# RA8D2_MCU_-_Ports.net
KiCad netlist of a schematic drawn in Altium Designer
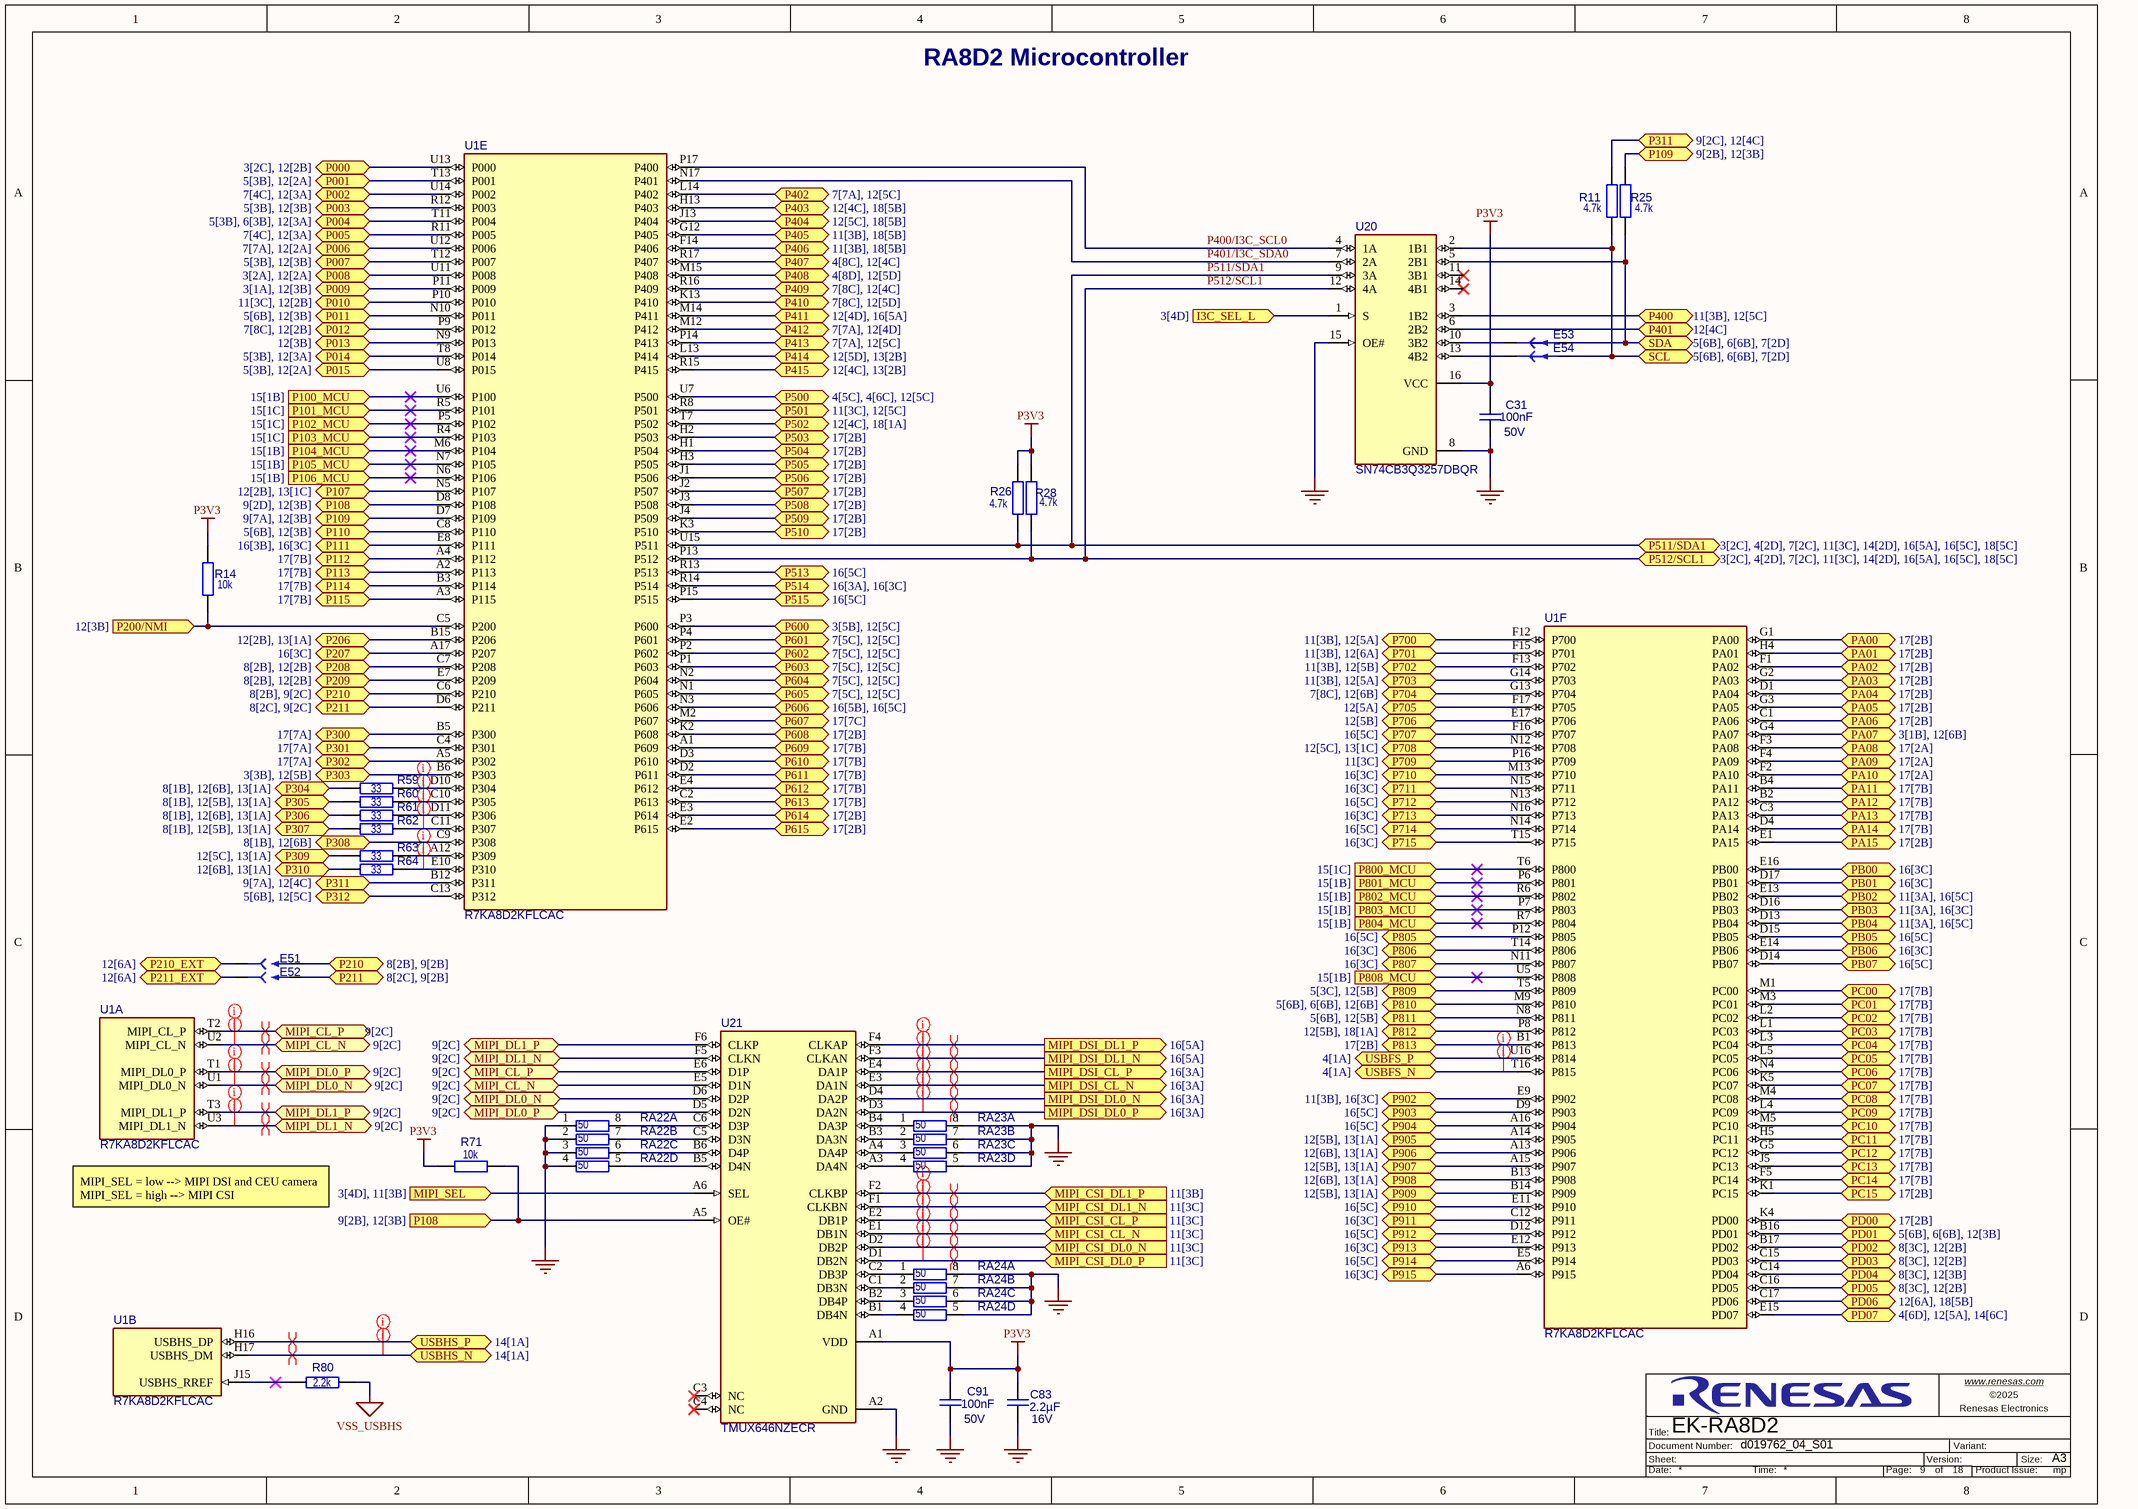
[diagram p0: RA8D2 MCU - Ports.SchDoc]

(export (version "E")
  (design (tool "Eeschema 10.0.6"))
  (components
    (comp (ref "C31")
      (value "100nF")
      (footprint "C_EIA0402_0p55")
      (description "Capacitor,EIA0402,100n,50V,X7R")
      (fields
        (field (name "TOLERANCE") "10%")
        (field (name "OPERATING VOLTAGE MAX") "50V")
        (field (name "Comment") "Capacitor")
      )
      (libsource (lib "ek-ra8d2_mp - Customer") (part "Capacitor"))
    )
    (comp (ref "C83")
      (value "2.2µF")
      (footprint "C_EIA0402_0p7")
      (description "Capacitor,EIA0402,2.2u,16V,X6S")
      (fields
        (field (name "TOLERANCE") "10%")
        (field (name "OPERATING VOLTAGE MAX") "16V")
        (field (name "Comment") "Capacitor")
      )
      (libsource (lib "ek-ra8d2_mp - Customer") (part "Capacitor"))
    )
    (comp (ref "C91")
      (value "100nF")
      (footprint "C_EIA0402_0p55")
      (description "Capacitor,EIA0402,100n,50V,X7R")
      (fields
        (field (name "TOLERANCE") "10%")
        (field (name "OPERATING VOLTAGE MAX") "50V")
        (field (name "Comment") "Capacitor")
      )
      (libsource (lib "ek-ra8d2_mp - Customer") (part "Capacitor"))
    )
    (comp (ref "E51")
      (value "SOLDER_BRIDGE_0805")
      (footprint "solder_bridge_0805")
      (description "Solder Bridge, SMD, 0805 size")
      (libsource (lib "ek-ra8d2_mp - Customer") (part "solder_bridge"))
    )
    (comp (ref "E52")
      (value "SOLDER_BRIDGE_0805")
      (footprint "solder_bridge_0805")
      (description "Solder Bridge, SMD, 0805 size")
      (libsource (lib "ek-ra8d2_mp - Customer") (part "solder_bridge"))
    )
    (comp (ref "E53")
      (value "TRACE_CUT_0805")
      (footprint "trace_cut_0805")
      (description "Trace Cut, SMD, 0805 size")
      (libsource (lib "ek-ra8d2_mp - Customer") (part "trace_cut"))
    )
    (comp (ref "E54")
      (value "TRACE_CUT_0805")
      (footprint "trace_cut_0805")
      (description "Trace Cut, SMD, 0805 size")
      (libsource (lib "ek-ra8d2_mp - Customer") (part "trace_cut"))
    )
    (comp (ref "R11")
      (value "4.7k")
      (footprint "R_EIA0402")
      (description "Resistor,EIA0402,4.7k,0.0625W")
      (fields (field (name "POWER") "62.5mW") (field (name "TOLERANCE") "1%"))
      (libsource (lib "") (part "Resistor_2"))
    )
    (comp (ref "R14")
      (value "10k")
      (footprint "R_EIA0402")
      (description "Resistor,EIA0402,10k,0.0625W")
      (fields (field (name "POWER") "62.5mW") (field (name "TOLERANCE") "1%"))
      (libsource (lib "") (part "Resistor_2"))
    )
    (comp (ref "R25")
      (value "4.7k")
      (footprint "R_EIA0402")
      (description "Resistor,EIA0402,4.7k,0.0625W")
      (fields (field (name "POWER") "62.5mW") (field (name "TOLERANCE") "1%"))
      (libsource (lib "") (part "Resistor_2"))
    )
    (comp (ref "R26")
      (value "4.7k")
      (footprint "R_EIA0402")
      (description "Resistor,EIA0402,4.7k,0.0625W")
      (fields (field (name "POWER") "62.5mW") (field (name "TOLERANCE") "1%"))
      (libsource (lib "") (part "Resistor_2"))
    )
    (comp (ref "R28")
      (value "4.7k")
      (footprint "R_EIA0402")
      (description "Resistor,EIA0402,4.7k,0.0625W")
      (fields (field (name "POWER") "62.5mW") (field (name "TOLERANCE") "1%"))
      (libsource (lib "") (part "Resistor_2"))
    )
    (comp (ref "R59")
      (value "33")
      (footprint "R_EIA0402")
      (description "Resistor,EIA0402,33,0.0625W")
      (fields (field (name "POWER") "62.5mW") (field (name "TOLERANCE") "1%"))
      (libsource (lib "ek-ra8d2_mp - Customer") (part "Resistor"))
    )
    (comp (ref "R60")
      (value "33")
      (footprint "R_EIA0402")
      (description "Resistor,EIA0402,33,0.0625W")
      (fields (field (name "POWER") "62.5mW") (field (name "TOLERANCE") "1%"))
      (libsource (lib "ek-ra8d2_mp - Customer") (part "Resistor"))
    )
    (comp (ref "R61")
      (value "33")
      (footprint "R_EIA0402")
      (description "Resistor,EIA0402,33,0.0625W")
      (fields (field (name "POWER") "62.5mW") (field (name "TOLERANCE") "1%"))
      (libsource (lib "ek-ra8d2_mp - Customer") (part "Resistor"))
    )
    (comp (ref "R62")
      (value "33")
      (footprint "R_EIA0402")
      (description "Resistor,EIA0402,33,0.0625W")
      (fields (field (name "POWER") "62.5mW") (field (name "TOLERANCE") "1%"))
      (libsource (lib "ek-ra8d2_mp - Customer") (part "Resistor"))
    )
    (comp (ref "R63")
      (value "33")
      (footprint "R_EIA0402")
      (description "Resistor,EIA0402,33,0.0625W")
      (fields (field (name "POWER") "62.5mW") (field (name "TOLERANCE") "1%"))
      (libsource (lib "ek-ra8d2_mp - Customer") (part "Resistor"))
    )
    (comp (ref "R64")
      (value "33")
      (footprint "R_EIA0402")
      (description "Resistor,EIA0402,33,0.0625W")
      (fields (field (name "POWER") "62.5mW") (field (name "TOLERANCE") "1%"))
      (libsource (lib "ek-ra8d2_mp - Customer") (part "Resistor"))
    )
    (comp (ref "R71")
      (value "10k")
      (footprint "R_EIA0402")
      (description "Resistor,EIA0402,10k,0.0625W")
      (fields (field (name "POWER") "62.5mW") (field (name "TOLERANCE") "1%"))
      (libsource (lib "ek-ra8d2_mp - Customer") (part "Resistor"))
    )
    (comp (ref "R80")
      (value "2.2k")
      (footprint "R_EIA0402")
      (description "Resistor,EIA0402,2.2k,0.0625W")
      (fields (field (name "POWER") "62.5mW") (field (name "TOLERANCE") "1%"))
      (libsource (lib "") (part "Resistor_1"))
    )
    (comp (ref "RA22")
      (value "50")
      (footprint "R_Array_EIA0804")
      (description "Resistor Network & Array,0804, 50,0.0625W")
      (fields (field (name "TOLERANCE") "1%") (field (name "POWER") "62mW"))
      (libsource (lib "ek-ra8d2_mp - Customer") (part "Resistor_Array"))
    )
    (comp (ref "RA23")
      (value "50")
      (footprint "R_Array_EIA0804")
      (description "Resistor Network & Array,0804, 50,0.0625W")
      (fields (field (name "TOLERANCE") "1%") (field (name "POWER") "62mW"))
      (libsource (lib "ek-ra8d2_mp - Customer") (part "Resistor_Array"))
    )
    (comp (ref "RA24")
      (value "50")
      (footprint "R_Array_EIA0804")
      (description "Resistor Network & Array,0804, 50,0.0625W")
      (fields (field (name "TOLERANCE") "1%") (field (name "POWER") "62mW"))
      (libsource (lib "ek-ra8d2_mp - Customer") (part "Resistor_Array"))
    )
    (comp (ref "U1")
      (value "R7KA8D2KFLCAC")
      (footprint "ren_bga289_PRBG0289JA-A")
      (libsource (lib "ek-ra8d2_mp - Customer") (part "ren_R7KA8D2KFLCAC"))
    )
    (comp (ref "U20")
      (value "SN74CB3Q3257DBQR")
      (footprint "ti_SSOP-16_4.9x3.9mm")
      (description "4-Bit 1-of-2 FET Multiplexer/Demultiplexer 2.5-V/3.3-V Low-Voltage High-Bandwidth Bus Switch")
      (libsource (lib "ek-ra8d2_mp - Customer") (part "ti_SN74CB3Q3257"))
    )
    (comp (ref "U21")
      (value "TMUX646NZECR")
      (footprint "ti_NFBGA-36_ZEC0036A")
      (description "6-GHz, 5-V, 2: 1 (SPDT) 10-channel MIPI switch with 1.8-V logic support 36-NFBGA -40 to 85")
      (libsource (lib "ek-ra8d2_mp - Customer") (part "ti_TMUX646"))
    )
  )
  (nets
    (net (code "1") (name "/I3C_SEL_L") (class "Default")
      (node (ref "U20") (pin "1") (pinfunction "S_1") (pintype "input"))
    )
    (net (code "2") (name "/MIPI_CL_N") (class "Default")
      (node (ref "U1") (pin "U2") (pinfunction "MIPI_CL_N_U2") (pintype "bidirectional"))
      (node (ref "U21") (pin "E5") (pinfunction "D1N_E5") (pintype "bidirectional"))
    )
    (net (code "3") (name "/MIPI_CL_P") (class "Default")
      (node (ref "U1") (pin "T2") (pinfunction "MIPI_CL_P_T2") (pintype "bidirectional"))
      (node (ref "U21") (pin "E6") (pinfunction "D1P_E6") (pintype "bidirectional"))
    )
    (net (code "4") (name "/MIPI_CSI_CL_N") (class "Default")
      (node (ref "U21") (pin "E1") (pinfunction "DB1N_E1") (pintype "bidirectional"))
    )
    (net (code "5") (name "/MIPI_CSI_CL_P") (class "Default")
      (node (ref "U21") (pin "E2") (pinfunction "DB1P_E2") (pintype "bidirectional"))
    )
    (net (code "6") (name "/MIPI_CSI_DL0_N") (class "Default")
      (node (ref "U21") (pin "D2") (pinfunction "DB2P_D2") (pintype "bidirectional"))
    )
    (net (code "7") (name "/MIPI_CSI_DL0_P") (class "Default")
      (node (ref "U21") (pin "D1") (pinfunction "DB2N_D1") (pintype "bidirectional"))
    )
    (net (code "8") (name "/MIPI_CSI_DL1_N") (class "Default")
      (node (ref "U21") (pin "F1") (pinfunction "CLKBN_F1") (pintype "bidirectional"))
    )
    (net (code "9") (name "/MIPI_CSI_DL1_P") (class "Default")
      (node (ref "U21") (pin "F2") (pinfunction "CLKBP_F2") (pintype "bidirectional"))
    )
    (net (code "10") (name "/MIPI_DL0_N") (class "Default")
      (node (ref "U1") (pin "U1") (pinfunction "MIPI_DL0_N_U1") (pintype "bidirectional"))
      (node (ref "U21") (pin "D6") (pinfunction "D2P_D6") (pintype "bidirectional"))
    )
    (net (code "11") (name "/MIPI_DL0_P") (class "Default")
      (node (ref "U1") (pin "T1") (pinfunction "MIPI_DL0_P_T1") (pintype "bidirectional"))
      (node (ref "U21") (pin "D5") (pinfunction "D2N_D5") (pintype "bidirectional"))
    )
    (net (code "12") (name "/MIPI_DL1_N") (class "Default")
      (node (ref "U1") (pin "U3") (pinfunction "MIPI_DL1_N_U3") (pintype "bidirectional"))
      (node (ref "U21") (pin "F5") (pinfunction "CLKN_F5") (pintype "bidirectional"))
    )
    (net (code "13") (name "/MIPI_DL1_P") (class "Default")
      (node (ref "U1") (pin "T3") (pinfunction "MIPI_DL1_P_T3") (pintype "bidirectional"))
      (node (ref "U21") (pin "F6") (pinfunction "CLKP_F6") (pintype "bidirectional"))
    )
    (net (code "14") (name "/MIPI_DSI_CL_N") (class "Default")
      (node (ref "U21") (pin "E3") (pinfunction "DA1N_E3") (pintype "bidirectional"))
    )
    (net (code "15") (name "/MIPI_DSI_CL_P") (class "Default")
      (node (ref "U21") (pin "E4") (pinfunction "DA1P_E4") (pintype "bidirectional"))
    )
    (net (code "16") (name "/MIPI_DSI_DL0_N") (class "Default")
      (node (ref "U21") (pin "D4") (pinfunction "DA2P_D4") (pintype "bidirectional"))
    )
    (net (code "17") (name "/MIPI_DSI_DL0_P") (class "Default")
      (node (ref "U21") (pin "D3") (pinfunction "DA2N_D3") (pintype "bidirectional"))
    )
    (net (code "18") (name "/MIPI_DSI_DL1_N") (class "Default")
      (node (ref "U21") (pin "F3") (pinfunction "CLKAN_F3") (pintype "bidirectional"))
    )
    (net (code "19") (name "/MIPI_DSI_DL1_P") (class "Default")
      (node (ref "U21") (pin "F4") (pinfunction "CLKAP_F4") (pintype "bidirectional"))
    )
    (net (code "20") (name "/MIPI_SEL") (class "Default")
      (node (ref "U21") (pin "A6") (pinfunction "SEL_A6") (pintype "input"))
    )
    (net (code "21") (name "/P000") (class "Default")
      (node (ref "U1") (pin "U13") (pinfunction "P000_U13") (pintype "bidirectional"))
    )
    (net (code "22") (name "/P001") (class "Default")
      (node (ref "U1") (pin "T13") (pinfunction "P001_T13") (pintype "bidirectional"))
    )
    (net (code "23") (name "/P002") (class "Default")
      (node (ref "U1") (pin "U14") (pinfunction "P002_U14") (pintype "bidirectional"))
    )
    (net (code "24") (name "/P003") (class "Default")
      (node (ref "U1") (pin "R12") (pinfunction "P003_R12") (pintype "bidirectional"))
    )
    (net (code "25") (name "/P004") (class "Default")
      (node (ref "U1") (pin "T11") (pinfunction "P004_T11") (pintype "bidirectional"))
    )
    (net (code "26") (name "/P005") (class "Default")
      (node (ref "U1") (pin "R11") (pinfunction "P005_R11") (pintype "bidirectional"))
    )
    (net (code "27") (name "/P006") (class "Default")
      (node (ref "U1") (pin "U12") (pinfunction "P006_U12") (pintype "bidirectional"))
    )
    (net (code "28") (name "/P007") (class "Default")
      (node (ref "U1") (pin "T12") (pinfunction "P007_T12") (pintype "bidirectional"))
    )
    (net (code "29") (name "/P008") (class "Default")
      (node (ref "U1") (pin "U11") (pinfunction "P008_U11") (pintype "bidirectional"))
    )
    (net (code "30") (name "/P009") (class "Default")
      (node (ref "U1") (pin "P11") (pinfunction "P009_P11") (pintype "bidirectional"))
    )
    (net (code "31") (name "/P010") (class "Default")
      (node (ref "U1") (pin "P10") (pinfunction "P010_P10") (pintype "bidirectional"))
    )
    (net (code "32") (name "/P011") (class "Default")
      (node (ref "U1") (pin "N10") (pinfunction "P011_N10") (pintype "bidirectional"))
    )
    (net (code "33") (name "/P012") (class "Default")
      (node (ref "U1") (pin "P9") (pinfunction "P012_P9") (pintype "bidirectional"))
    )
    (net (code "34") (name "/P013") (class "Default")
      (node (ref "U1") (pin "N9") (pinfunction "P013_N9") (pintype "bidirectional"))
    )
    (net (code "35") (name "/P014") (class "Default")
      (node (ref "U1") (pin "T8") (pinfunction "P014_T8") (pintype "bidirectional"))
    )
    (net (code "36") (name "/P015") (class "Default")
      (node (ref "U1") (pin "U8") (pinfunction "P015_U8") (pintype "bidirectional"))
    )
    (net (code "37") (name "/P100_MCU") (class "Default")
      (node (ref "U1") (pin "U6") (pinfunction "P100_U6") (pintype "bidirectional"))
    )
    (net (code "38") (name "/P101_MCU") (class "Default")
      (node (ref "U1") (pin "R5") (pinfunction "P101_R5") (pintype "bidirectional"))
    )
    (net (code "39") (name "/P102_MCU") (class "Default")
      (node (ref "U1") (pin "P5") (pinfunction "P102_P5") (pintype "bidirectional"))
    )
    (net (code "40") (name "/P103_MCU") (class "Default")
      (node (ref "U1") (pin "R4") (pinfunction "P103_R4") (pintype "bidirectional"))
    )
    (net (code "41") (name "/P104_MCU") (class "Default")
      (node (ref "U1") (pin "M6") (pinfunction "P104_M6") (pintype "bidirectional"))
    )
    (net (code "42") (name "/P105_MCU") (class "Default")
      (node (ref "U1") (pin "N7") (pinfunction "P105_N7") (pintype "bidirectional"))
    )
    (net (code "43") (name "/P106_MCU") (class "Default")
      (node (ref "U1") (pin "N6") (pinfunction "P106_N6") (pintype "bidirectional"))
    )
    (net (code "44") (name "/P107") (class "Default")
      (node (ref "U1") (pin "N5") (pinfunction "P107_N5") (pintype "bidirectional"))
    )
    (net (code "45") (name "/P108") (class "Default")
      (node (ref "R71") (pin "2") (pinfunction "2_2") (pintype "passive"))
      (node (ref "U1") (pin "D8") (pinfunction "P108_D8") (pintype "bidirectional"))
      (node (ref "U21") (pin "A5") (pinfunction "OE#_A5") (pintype "input"))
    )
    (net (code "46") (name "/P109") (class "Default")
      (node (ref "R25") (pin "2") (pinfunction "2_2") (pintype "passive"))
      (node (ref "U1") (pin "D7") (pinfunction "P109_D7") (pintype "bidirectional"))
    )
    (net (code "47") (name "/P110") (class "Default")
      (node (ref "U1") (pin "C8") (pinfunction "P110_C8") (pintype "bidirectional"))
    )
    (net (code "48") (name "/P111") (class "Default")
      (node (ref "U1") (pin "E8") (pinfunction "P111_E8") (pintype "bidirectional"))
    )
    (net (code "49") (name "/P112") (class "Default")
      (node (ref "U1") (pin "A4") (pinfunction "P112_A4") (pintype "bidirectional"))
    )
    (net (code "50") (name "/P113") (class "Default")
      (node (ref "U1") (pin "A2") (pinfunction "P113_A2") (pintype "bidirectional"))
    )
    (net (code "51") (name "/P114") (class "Default")
      (node (ref "U1") (pin "B3") (pinfunction "P114_B3") (pintype "bidirectional"))
    )
    (net (code "52") (name "/P115") (class "Default")
      (node (ref "U1") (pin "A3") (pinfunction "P115_A3") (pintype "bidirectional"))
    )
    (net (code "53") (name "/P200{slash}NMI") (class "Default")
      (node (ref "R14") (pin "1") (pinfunction "1_1") (pintype "passive"))
      (node (ref "U1") (pin "C5") (pinfunction "P200_C5") (pintype "bidirectional"))
    )
    (net (code "54") (name "/P206") (class "Default")
      (node (ref "U1") (pin "B15") (pinfunction "P206_B15") (pintype "bidirectional"))
    )
    (net (code "55") (name "/P207") (class "Default")
      (node (ref "U1") (pin "A17") (pinfunction "P207_A17") (pintype "bidirectional"))
    )
    (net (code "56") (name "/P208") (class "Default")
      (node (ref "U1") (pin "C7") (pinfunction "P208_C7") (pintype "bidirectional"))
    )
    (net (code "57") (name "/P209") (class "Default")
      (node (ref "U1") (pin "E7") (pinfunction "P209_E7") (pintype "bidirectional"))
    )
    (net (code "58") (name "/P210") (class "Default")
      (node (ref "E51") (pin "2") (pinfunction "2_2") (pintype "passive"))
      (node (ref "U1") (pin "C6") (pinfunction "P210_C6") (pintype "bidirectional"))
    )
    (net (code "59") (name "/P210_EXT") (class "Default")
      (node (ref "E51") (pin "1") (pinfunction "1_1") (pintype "passive"))
    )
    (net (code "60") (name "/P211") (class "Default")
      (node (ref "E52") (pin "2") (pinfunction "2_2") (pintype "passive"))
      (node (ref "U1") (pin "D6") (pinfunction "P211_D6") (pintype "bidirectional"))
    )
    (net (code "61") (name "/P211_EXT") (class "Default")
      (node (ref "E52") (pin "1") (pinfunction "1_1") (pintype "passive"))
    )
    (net (code "62") (name "/P300") (class "Default")
      (node (ref "U1") (pin "B5") (pinfunction "P300_B5") (pintype "bidirectional"))
    )
    (net (code "63") (name "/P301") (class "Default")
      (node (ref "U1") (pin "C4") (pinfunction "P301_C4") (pintype "bidirectional"))
    )
    (net (code "64") (name "/P302") (class "Default")
      (node (ref "U1") (pin "A5") (pinfunction "P302_A5") (pintype "bidirectional"))
    )
    (net (code "65") (name "/P303") (class "Default")
      (node (ref "U1") (pin "B6") (pinfunction "P303_B6") (pintype "bidirectional"))
    )
    (net (code "66") (name "/P304") (class "Default")
      (node (ref "R59") (pin "1") (pinfunction "1_1") (pintype "passive"))
    )
    (net (code "67") (name "/P305") (class "Default")
      (node (ref "R60") (pin "1") (pinfunction "1_1") (pintype "passive"))
    )
    (net (code "68") (name "/P306") (class "Default")
      (node (ref "R61") (pin "1") (pinfunction "1_1") (pintype "passive"))
    )
    (net (code "69") (name "/P307") (class "Default")
      (node (ref "R62") (pin "1") (pinfunction "1_1") (pintype "passive"))
    )
    (net (code "70") (name "/P308") (class "Default")
      (node (ref "U1") (pin "C9") (pinfunction "P308_C9") (pintype "bidirectional"))
    )
    (net (code "71") (name "/P309") (class "Default")
      (node (ref "R63") (pin "1") (pinfunction "1_1") (pintype "passive"))
    )
    (net (code "72") (name "/P310") (class "Default")
      (node (ref "R64") (pin "1") (pinfunction "1_1") (pintype "passive"))
    )
    (net (code "73") (name "/P311") (class "Default")
      (node (ref "R11") (pin "2") (pinfunction "2_2") (pintype "passive"))
      (node (ref "U1") (pin "B12") (pinfunction "P311_B12") (pintype "bidirectional"))
    )
    (net (code "74") (name "/P312") (class "Default")
      (node (ref "U1") (pin "C13") (pinfunction "P312_C13") (pintype "bidirectional"))
    )
    (net (code "75") (name "/P400") (class "Default")
      (node (ref "U20") (pin "3") (pinfunction "1B2_3") (pintype "bidirectional"))
    )
    (net (code "76") (name "/P400{slash}I3C_SCL0") (class "Default")
      (node (ref "U1") (pin "P17") (pinfunction "P400_P17") (pintype "bidirectional"))
      (node (ref "U20") (pin "4") (pinfunction "1A_4") (pintype "bidirectional"))
    )
    (net (code "77") (name "/P401") (class "Default")
      (node (ref "U20") (pin "6") (pinfunction "2B2_6") (pintype "bidirectional"))
    )
    (net (code "78") (name "/P401{slash}I3C_SDA0") (class "Default")
      (node (ref "U1") (pin "N17") (pinfunction "P401_N17") (pintype "bidirectional"))
      (node (ref "U20") (pin "7") (pinfunction "2A_7") (pintype "bidirectional"))
    )
    (net (code "79") (name "/P402") (class "Default")
      (node (ref "U1") (pin "L14") (pinfunction "P402_L14") (pintype "bidirectional"))
    )
    (net (code "80") (name "/P403") (class "Default")
      (node (ref "U1") (pin "H13") (pinfunction "P403_H13") (pintype "bidirectional"))
    )
    (net (code "81") (name "/P404") (class "Default")
      (node (ref "U1") (pin "J13") (pinfunction "P404_J13") (pintype "bidirectional"))
    )
    (net (code "82") (name "/P405") (class "Default")
      (node (ref "U1") (pin "G12") (pinfunction "P405_G12") (pintype "bidirectional"))
    )
    (net (code "83") (name "/P406") (class "Default")
      (node (ref "U1") (pin "F14") (pinfunction "P406_F14") (pintype "bidirectional"))
    )
    (net (code "84") (name "/P407") (class "Default")
      (node (ref "U1") (pin "R17") (pinfunction "P407_R17") (pintype "bidirectional"))
    )
    (net (code "85") (name "/P408") (class "Default")
      (node (ref "U1") (pin "M15") (pinfunction "P408_M15") (pintype "bidirectional"))
    )
    (net (code "86") (name "/P409") (class "Default")
      (node (ref "U1") (pin "R16") (pinfunction "P409_R16") (pintype "bidirectional"))
    )
    (net (code "87") (name "/P410") (class "Default")
      (node (ref "U1") (pin "K13") (pinfunction "P410_K13") (pintype "bidirectional"))
    )
    (net (code "88") (name "/P411") (class "Default")
      (node (ref "U1") (pin "M14") (pinfunction "P411_M14") (pintype "bidirectional"))
    )
    (net (code "89") (name "/P412") (class "Default")
      (node (ref "U1") (pin "M12") (pinfunction "P412_M12") (pintype "bidirectional"))
    )
    (net (code "90") (name "/P413") (class "Default")
      (node (ref "U1") (pin "P14") (pinfunction "P413_P14") (pintype "bidirectional"))
    )
    (net (code "91") (name "/P414") (class "Default")
      (node (ref "U1") (pin "L13") (pinfunction "P414_L13") (pintype "bidirectional"))
    )
    (net (code "92") (name "/P415") (class "Default")
      (node (ref "U1") (pin "R15") (pinfunction "P415_R15") (pintype "bidirectional"))
    )
    (net (code "93") (name "/P500") (class "Default")
      (node (ref "U1") (pin "U7") (pinfunction "P500_U7") (pintype "bidirectional"))
    )
    (net (code "94") (name "/P501") (class "Default")
      (node (ref "U1") (pin "R8") (pinfunction "P501_R8") (pintype "bidirectional"))
    )
    (net (code "95") (name "/P502") (class "Default")
      (node (ref "U1") (pin "T7") (pinfunction "P502_T7") (pintype "bidirectional"))
    )
    (net (code "96") (name "/P503") (class "Default")
      (node (ref "U1") (pin "H2") (pinfunction "P503_H2") (pintype "bidirectional"))
    )
    (net (code "97") (name "/P504") (class "Default")
      (node (ref "U1") (pin "H1") (pinfunction "P504_H1") (pintype "bidirectional"))
    )
    (net (code "98") (name "/P505") (class "Default")
      (node (ref "U1") (pin "H3") (pinfunction "P505_H3") (pintype "bidirectional"))
    )
    (net (code "99") (name "/P506") (class "Default")
      (node (ref "U1") (pin "J1") (pinfunction "P506_J1") (pintype "bidirectional"))
    )
    (net (code "100") (name "/P507") (class "Default")
      (node (ref "U1") (pin "J2") (pinfunction "P507_J2") (pintype "bidirectional"))
    )
    (net (code "101") (name "/P508") (class "Default")
      (node (ref "U1") (pin "J3") (pinfunction "P508_J3") (pintype "bidirectional"))
    )
    (net (code "102") (name "/P509") (class "Default")
      (node (ref "U1") (pin "J4") (pinfunction "P509_J4") (pintype "bidirectional"))
    )
    (net (code "103") (name "/P510") (class "Default")
      (node (ref "U1") (pin "K3") (pinfunction "P510_K3") (pintype "bidirectional"))
    )
    (net (code "104") (name "/P511{slash}SDA1") (class "Default")
      (node (ref "R26") (pin "1") (pinfunction "1_1") (pintype "passive"))
      (node (ref "U1") (pin "U15") (pinfunction "P511_U15") (pintype "bidirectional"))
      (node (ref "U20") (pin "9") (pinfunction "3A_9") (pintype "bidirectional"))
    )
    (net (code "105") (name "/P512{slash}SCL1") (class "Default")
      (node (ref "R28") (pin "1") (pinfunction "1_1") (pintype "passive"))
      (node (ref "U1") (pin "P13") (pinfunction "P512_P13") (pintype "bidirectional"))
      (node (ref "U20") (pin "12") (pinfunction "4A_12") (pintype "bidirectional"))
    )
    (net (code "106") (name "/P513") (class "Default")
      (node (ref "U1") (pin "R13") (pinfunction "P513_R13") (pintype "bidirectional"))
    )
    (net (code "107") (name "/P514") (class "Default")
      (node (ref "U1") (pin "R14") (pinfunction "P514_R14") (pintype "bidirectional"))
    )
    (net (code "108") (name "/P515") (class "Default")
      (node (ref "U1") (pin "P15") (pinfunction "P515_P15") (pintype "bidirectional"))
    )
    (net (code "109") (name "/P600") (class "Default")
      (node (ref "U1") (pin "P3") (pinfunction "P600_P3") (pintype "bidirectional"))
    )
    (net (code "110") (name "/P601") (class "Default")
      (node (ref "U1") (pin "P4") (pinfunction "P601_P4") (pintype "bidirectional"))
    )
    (net (code "111") (name "/P602") (class "Default")
      (node (ref "U1") (pin "P2") (pinfunction "P602_P2") (pintype "bidirectional"))
    )
    (net (code "112") (name "/P603") (class "Default")
      (node (ref "U1") (pin "P1") (pinfunction "P603_P1") (pintype "bidirectional"))
    )
    (net (code "113") (name "/P604") (class "Default")
      (node (ref "U1") (pin "N2") (pinfunction "P604_N2") (pintype "bidirectional"))
    )
    (net (code "114") (name "/P605") (class "Default")
      (node (ref "U1") (pin "N1") (pinfunction "P605_N1") (pintype "bidirectional"))
    )
    (net (code "115") (name "/P606") (class "Default")
      (node (ref "U1") (pin "N3") (pinfunction "P606_N3") (pintype "bidirectional"))
    )
    (net (code "116") (name "/P607") (class "Default")
      (node (ref "U1") (pin "M2") (pinfunction "P607_M2") (pintype "bidirectional"))
    )
    (net (code "117") (name "/P608") (class "Default")
      (node (ref "U1") (pin "K2") (pinfunction "P608_K2") (pintype "bidirectional"))
    )
    (net (code "118") (name "/P609") (class "Default")
      (node (ref "U1") (pin "A1") (pinfunction "P609_A1") (pintype "bidirectional"))
    )
    (net (code "119") (name "/P610") (class "Default")
      (node (ref "U1") (pin "D3") (pinfunction "P610_D3") (pintype "bidirectional"))
    )
    (net (code "120") (name "/P611") (class "Default")
      (node (ref "U1") (pin "D2") (pinfunction "P611_D2") (pintype "bidirectional"))
    )
    (net (code "121") (name "/P612") (class "Default")
      (node (ref "U1") (pin "E4") (pinfunction "P612_E4") (pintype "bidirectional"))
    )
    (net (code "122") (name "/P613") (class "Default")
      (node (ref "U1") (pin "C2") (pinfunction "P613_C2") (pintype "bidirectional"))
    )
    (net (code "123") (name "/P614") (class "Default")
      (node (ref "U1") (pin "E3") (pinfunction "P614_E3") (pintype "bidirectional"))
    )
    (net (code "124") (name "/P615") (class "Default")
      (node (ref "U1") (pin "E2") (pinfunction "P615_E2") (pintype "bidirectional"))
    )
    (net (code "125") (name "/P700") (class "Default")
      (node (ref "U1") (pin "F12") (pinfunction "P700_F12") (pintype "bidirectional"))
    )
    (net (code "126") (name "/P701") (class "Default")
      (node (ref "U1") (pin "F15") (pinfunction "P701_F15") (pintype "bidirectional"))
    )
    (net (code "127") (name "/P702") (class "Default")
      (node (ref "U1") (pin "F13") (pinfunction "P702_F13") (pintype "bidirectional"))
    )
    (net (code "128") (name "/P703") (class "Default")
      (node (ref "U1") (pin "G14") (pinfunction "P703_G14") (pintype "bidirectional"))
    )
    (net (code "129") (name "/P704") (class "Default")
      (node (ref "U1") (pin "G13") (pinfunction "P704_G13") (pintype "bidirectional"))
    )
    (net (code "130") (name "/P705") (class "Default")
      (node (ref "U1") (pin "F17") (pinfunction "P705_F17") (pintype "bidirectional"))
    )
    (net (code "131") (name "/P706") (class "Default")
      (node (ref "U1") (pin "E17") (pinfunction "P706_E17") (pintype "bidirectional"))
    )
    (net (code "132") (name "/P707") (class "Default")
      (node (ref "U1") (pin "F16") (pinfunction "P707_F16") (pintype "bidirectional"))
    )
    (net (code "133") (name "/P708") (class "Default")
      (node (ref "U1") (pin "N12") (pinfunction "P708_N12") (pintype "bidirectional"))
    )
    (net (code "134") (name "/P709") (class "Default")
      (node (ref "U1") (pin "P16") (pinfunction "P709_P16") (pintype "bidirectional"))
    )
    (net (code "135") (name "/P710") (class "Default")
      (node (ref "U1") (pin "M13") (pinfunction "P710_M13") (pintype "bidirectional"))
    )
    (net (code "136") (name "/P711") (class "Default")
      (node (ref "U1") (pin "N15") (pinfunction "P711_N15") (pintype "bidirectional"))
    )
    (net (code "137") (name "/P712") (class "Default")
      (node (ref "U1") (pin "N13") (pinfunction "P712_N13") (pintype "bidirectional"))
    )
    (net (code "138") (name "/P713") (class "Default")
      (node (ref "U1") (pin "N16") (pinfunction "P713_N16") (pintype "bidirectional"))
    )
    (net (code "139") (name "/P714") (class "Default")
      (node (ref "U1") (pin "N14") (pinfunction "P714_N14") (pintype "bidirectional"))
    )
    (net (code "140") (name "/P715") (class "Default")
      (node (ref "U1") (pin "T15") (pinfunction "P715_T15") (pintype "bidirectional"))
    )
    (net (code "141") (name "/P800_MCU") (class "Default")
      (node (ref "U1") (pin "T6") (pinfunction "P800_T6") (pintype "bidirectional"))
    )
    (net (code "142") (name "/P801_MCU") (class "Default")
      (node (ref "U1") (pin "P6") (pinfunction "P801_P6") (pintype "bidirectional"))
    )
    (net (code "143") (name "/P802_MCU") (class "Default")
      (node (ref "U1") (pin "R6") (pinfunction "P802_R6") (pintype "bidirectional"))
    )
    (net (code "144") (name "/P803_MCU") (class "Default")
      (node (ref "U1") (pin "P7") (pinfunction "P803_P7") (pintype "bidirectional"))
    )
    (net (code "145") (name "/P804_MCU") (class "Default")
      (node (ref "U1") (pin "R7") (pinfunction "P804_R7") (pintype "bidirectional"))
    )
    (net (code "146") (name "/P805") (class "Default")
      (node (ref "U1") (pin "P12") (pinfunction "P805_P12") (pintype "bidirectional"))
    )
    (net (code "147") (name "/P806") (class "Default")
      (node (ref "U1") (pin "T14") (pinfunction "P806_T14") (pintype "bidirectional"))
    )
    (net (code "148") (name "/P807") (class "Default")
      (node (ref "U1") (pin "N11") (pinfunction "P807_N11") (pintype "bidirectional"))
    )
    (net (code "149") (name "/P808_MCU") (class "Default")
      (node (ref "U1") (pin "U5") (pinfunction "P808_U5") (pintype "bidirectional"))
    )
    (net (code "150") (name "/P809") (class "Default")
      (node (ref "U1") (pin "T5") (pinfunction "P809_T5") (pintype "bidirectional"))
    )
    (net (code "151") (name "/P810") (class "Default")
      (node (ref "U1") (pin "M9") (pinfunction "P810_M9") (pintype "bidirectional"))
    )
    (net (code "152") (name "/P811") (class "Default")
      (node (ref "U1") (pin "N8") (pinfunction "P811_N8") (pintype "bidirectional"))
    )
    (net (code "153") (name "/P812") (class "Default")
      (node (ref "U1") (pin "P8") (pinfunction "P812_P8") (pintype "bidirectional"))
    )
    (net (code "154") (name "/P813") (class "Default")
      (node (ref "U1") (pin "B1") (pinfunction "P813_B1") (pintype "bidirectional"))
    )
    (net (code "155") (name "/P902") (class "Default")
      (node (ref "U1") (pin "E9") (pinfunction "P902_E9") (pintype "bidirectional"))
    )
    (net (code "156") (name "/P903") (class "Default")
      (node (ref "U1") (pin "D9") (pinfunction "P903_D9") (pintype "bidirectional"))
    )
    (net (code "157") (name "/P904") (class "Default")
      (node (ref "U1") (pin "A16") (pinfunction "P904_A16") (pintype "bidirectional"))
    )
    (net (code "158") (name "/P905") (class "Default")
      (node (ref "U1") (pin "A14") (pinfunction "P905_A14") (pintype "bidirectional"))
    )
    (net (code "159") (name "/P906") (class "Default")
      (node (ref "U1") (pin "A13") (pinfunction "P906_A13") (pintype "bidirectional"))
    )
    (net (code "160") (name "/P907") (class "Default")
      (node (ref "U1") (pin "A15") (pinfunction "P907_A15") (pintype "bidirectional"))
    )
    (net (code "161") (name "/P908") (class "Default")
      (node (ref "U1") (pin "B13") (pinfunction "P908_B13") (pintype "bidirectional"))
    )
    (net (code "162") (name "/P909") (class "Default")
      (node (ref "U1") (pin "B14") (pinfunction "P909_B14") (pintype "bidirectional"))
    )
    (net (code "163") (name "/P910") (class "Default")
      (node (ref "U1") (pin "E11") (pinfunction "P910_E11") (pintype "bidirectional"))
    )
    (net (code "164") (name "/P911") (class "Default")
      (node (ref "U1") (pin "C12") (pinfunction "P911_C12") (pintype "bidirectional"))
    )
    (net (code "165") (name "/P912") (class "Default")
      (node (ref "U1") (pin "D12") (pinfunction "P912_D12") (pintype "bidirectional"))
    )
    (net (code "166") (name "/P913") (class "Default")
      (node (ref "U1") (pin "E12") (pinfunction "P913_E12") (pintype "bidirectional"))
    )
    (net (code "167") (name "/P914") (class "Default")
      (node (ref "U1") (pin "E5") (pinfunction "P914_E5") (pintype "bidirectional"))
    )
    (net (code "168") (name "/P915") (class "Default")
      (node (ref "U1") (pin "A6") (pinfunction "P915_A6") (pintype "bidirectional"))
    )
    (net (code "169") (name "/PA00") (class "Default")
      (node (ref "U1") (pin "G1") (pinfunction "PA00_G1") (pintype "bidirectional"))
    )
    (net (code "170") (name "/PA01") (class "Default")
      (node (ref "U1") (pin "H4") (pinfunction "PA01_H4") (pintype "bidirectional"))
    )
    (net (code "171") (name "/PA02") (class "Default")
      (node (ref "U1") (pin "F1") (pinfunction "PA02_F1") (pintype "bidirectional"))
    )
    (net (code "172") (name "/PA03") (class "Default")
      (node (ref "U1") (pin "G2") (pinfunction "PA03_G2") (pintype "bidirectional"))
    )
    (net (code "173") (name "/PA04") (class "Default")
      (node (ref "U1") (pin "D1") (pinfunction "PA04_D1") (pintype "bidirectional"))
    )
    (net (code "174") (name "/PA05") (class "Default")
      (node (ref "U1") (pin "G3") (pinfunction "PA05_G3") (pintype "bidirectional"))
    )
    (net (code "175") (name "/PA06") (class "Default")
      (node (ref "U1") (pin "C1") (pinfunction "PA06_C1") (pintype "bidirectional"))
    )
    (net (code "176") (name "/PA07") (class "Default")
      (node (ref "U1") (pin "G4") (pinfunction "PA07_G4") (pintype "bidirectional"))
    )
    (net (code "177") (name "/PA08") (class "Default")
      (node (ref "U1") (pin "F3") (pinfunction "PA08_F3") (pintype "bidirectional"))
    )
    (net (code "178") (name "/PA09") (class "Default")
      (node (ref "U1") (pin "F4") (pinfunction "PA09_F4") (pintype "bidirectional"))
    )
    (net (code "179") (name "/PA10") (class "Default")
      (node (ref "U1") (pin "F2") (pinfunction "PA10_F2") (pintype "bidirectional"))
    )
    (net (code "180") (name "/PA11") (class "Default")
      (node (ref "U1") (pin "B4") (pinfunction "PA11_B4") (pintype "bidirectional"))
    )
    (net (code "181") (name "/PA12") (class "Default")
      (node (ref "U1") (pin "B2") (pinfunction "PA12_B2") (pintype "bidirectional"))
    )
    (net (code "182") (name "/PA13") (class "Default")
      (node (ref "U1") (pin "C3") (pinfunction "PA13_C3") (pintype "bidirectional"))
    )
    (net (code "183") (name "/PA14") (class "Default")
      (node (ref "U1") (pin "D4") (pinfunction "PA14_D4") (pintype "bidirectional"))
    )
    (net (code "184") (name "/PA15") (class "Default")
      (node (ref "U1") (pin "E1") (pinfunction "PA15_E1") (pintype "bidirectional"))
    )
    (net (code "185") (name "/PB00") (class "Default")
      (node (ref "U1") (pin "E16") (pinfunction "PB00_E16") (pintype "bidirectional"))
    )
    (net (code "186") (name "/PB01") (class "Default")
      (node (ref "U1") (pin "D17") (pinfunction "PB01_D17") (pintype "bidirectional"))
    )
    (net (code "187") (name "/PB02") (class "Default")
      (node (ref "U1") (pin "E13") (pinfunction "PB02_E13") (pintype "bidirectional"))
    )
    (net (code "188") (name "/PB03") (class "Default")
      (node (ref "U1") (pin "D16") (pinfunction "PB03_D16") (pintype "bidirectional"))
    )
    (net (code "189") (name "/PB04") (class "Default")
      (node (ref "U1") (pin "D13") (pinfunction "PB04_D13") (pintype "bidirectional"))
    )
    (net (code "190") (name "/PB05") (class "Default")
      (node (ref "U1") (pin "D15") (pinfunction "PB05_D15") (pintype "bidirectional"))
    )
    (net (code "191") (name "/PB06") (class "Default")
      (node (ref "U1") (pin "E14") (pinfunction "PB06_E14") (pintype "bidirectional"))
    )
    (net (code "192") (name "/PB07") (class "Default")
      (node (ref "U1") (pin "D14") (pinfunction "PB07_D14") (pintype "bidirectional"))
    )
    (net (code "193") (name "/PC00") (class "Default")
      (node (ref "U1") (pin "M1") (pinfunction "PC00_M1") (pintype "bidirectional"))
    )
    (net (code "194") (name "/PC01") (class "Default")
      (node (ref "U1") (pin "M3") (pinfunction "PC01_M3") (pintype "bidirectional"))
    )
    (net (code "195") (name "/PC02") (class "Default")
      (node (ref "U1") (pin "L2") (pinfunction "PC02_L2") (pintype "bidirectional"))
    )
    (net (code "196") (name "/PC03") (class "Default")
      (node (ref "U1") (pin "L1") (pinfunction "PC03_L1") (pintype "bidirectional"))
    )
    (net (code "197") (name "/PC04") (class "Default")
      (node (ref "U1") (pin "L3") (pinfunction "PC04_L3") (pintype "bidirectional"))
    )
    (net (code "198") (name "/PC05") (class "Default")
      (node (ref "U1") (pin "L5") (pinfunction "PC05_L5") (pintype "bidirectional"))
    )
    (net (code "199") (name "/PC06") (class "Default")
      (node (ref "U1") (pin "N4") (pinfunction "PC06_N4") (pintype "bidirectional"))
    )
    (net (code "200") (name "/PC07") (class "Default")
      (node (ref "U1") (pin "K5") (pinfunction "PC07_K5") (pintype "bidirectional"))
    )
    (net (code "201") (name "/PC08") (class "Default")
      (node (ref "U1") (pin "M4") (pinfunction "PC08_M4") (pintype "bidirectional"))
    )
    (net (code "202") (name "/PC09") (class "Default")
      (node (ref "U1") (pin "L4") (pinfunction "PC09_L4") (pintype "bidirectional"))
    )
    (net (code "203") (name "/PC10") (class "Default")
      (node (ref "U1") (pin "M5") (pinfunction "PC10_M5") (pintype "bidirectional"))
    )
    (net (code "204") (name "/PC11") (class "Default")
      (node (ref "U1") (pin "H5") (pinfunction "PC11_H5") (pintype "bidirectional"))
    )
    (net (code "205") (name "/PC12") (class "Default")
      (node (ref "U1") (pin "G5") (pinfunction "PC12_G5") (pintype "bidirectional"))
    )
    (net (code "206") (name "/PC13") (class "Default")
      (node (ref "U1") (pin "J5") (pinfunction "PC13_J5") (pintype "bidirectional"))
    )
    (net (code "207") (name "/PC14") (class "Default")
      (node (ref "U1") (pin "F5") (pinfunction "PC14_F5") (pintype "bidirectional"))
    )
    (net (code "208") (name "/PC15") (class "Default")
      (node (ref "U1") (pin "K1") (pinfunction "PC15_K1") (pintype "bidirectional"))
    )
    (net (code "209") (name "/PD00") (class "Default")
      (node (ref "U1") (pin "K4") (pinfunction "PD00_K4") (pintype "bidirectional"))
    )
    (net (code "210") (name "/PD01") (class "Default")
      (node (ref "U1") (pin "B16") (pinfunction "PD01_B16") (pintype "bidirectional"))
    )
    (net (code "211") (name "/PD02") (class "Default")
      (node (ref "U1") (pin "B17") (pinfunction "PD02_B17") (pintype "bidirectional"))
    )
    (net (code "212") (name "/PD03") (class "Default")
      (node (ref "U1") (pin "C15") (pinfunction "PD03_C15") (pintype "bidirectional"))
    )
    (net (code "213") (name "/PD04") (class "Default")
      (node (ref "U1") (pin "C14") (pinfunction "PD04_C14") (pintype "bidirectional"))
    )
    (net (code "214") (name "/PD05") (class "Default")
      (node (ref "U1") (pin "C16") (pinfunction "PD05_C16") (pintype "bidirectional"))
    )
    (net (code "215") (name "/PD06") (class "Default")
      (node (ref "U1") (pin "C17") (pinfunction "PD06_C17") (pintype "bidirectional"))
    )
    (net (code "216") (name "/PD07") (class "Default")
      (node (ref "U1") (pin "E15") (pinfunction "PD07_E15") (pintype "bidirectional"))
    )
    (net (code "217") (name "/SCL") (class "Default")
      (node (ref "E54") (pin "2") (pinfunction "2_2") (pintype "passive"))
      (node (ref "R11") (pin "1") (pinfunction "1_1") (pintype "passive"))
      (node (ref "U20") (pin "2") (pinfunction "1B1_2") (pintype "bidirectional"))
    )
    (net (code "218") (name "/SDA") (class "Default")
      (node (ref "E53") (pin "2") (pinfunction "2_2") (pintype "passive"))
      (node (ref "R25") (pin "1") (pinfunction "1_1") (pintype "passive"))
      (node (ref "U20") (pin "5") (pinfunction "2B1_5") (pintype "bidirectional"))
    )
    (net (code "219") (name "/USBFS_N") (class "Default")
      (node (ref "U1") (pin "T16") (pinfunction "P815_T16") (pintype "bidirectional"))
    )
    (net (code "220") (name "/USBFS_P") (class "Default")
      (node (ref "U1") (pin "U16") (pinfunction "P814_U16") (pintype "bidirectional"))
    )
    (net (code "221") (name "/USBHS_N") (class "Default")
      (node (ref "U1") (pin "H17") (pinfunction "USBHS_DM_H17") (pintype "bidirectional"))
    )
    (net (code "222") (name "/USBHS_P") (class "Default")
      (node (ref "U1") (pin "H16") (pinfunction "USBHS_DP_H16") (pintype "bidirectional"))
    )
    (net (code "223") (name "GND") (class "Default")
      (node (ref "C31") (pin "1") (pinfunction "1_1") (pintype "passive"))
      (node (ref "C83") (pin "1") (pinfunction "1_1") (pintype "passive"))
      (node (ref "C91") (pin "1") (pinfunction "1_1") (pintype "passive"))
      (node (ref "RA22") (pin "1") (pinfunction "1_1") (pintype "passive"))
      (node (ref "RA22") (pin "2") (pinfunction "2_2") (pintype "passive"))
      (node (ref "RA22") (pin "3") (pinfunction "3_3") (pintype "passive"))
      (node (ref "RA22") (pin "4") (pinfunction "4_4") (pintype "passive"))
      (node (ref "RA23") (pin "5") (pinfunction "5_5") (pintype "passive"))
      (node (ref "RA23") (pin "6") (pinfunction "6_6") (pintype "passive"))
      (node (ref "RA23") (pin "7") (pinfunction "7_7") (pintype "passive"))
      (node (ref "RA23") (pin "8") (pinfunction "8_8") (pintype "passive"))
      (node (ref "RA24") (pin "5") (pinfunction "5_5") (pintype "passive"))
      (node (ref "RA24") (pin "6") (pinfunction "6_6") (pintype "passive"))
      (node (ref "RA24") (pin "7") (pinfunction "7_7") (pintype "passive"))
      (node (ref "RA24") (pin "8") (pinfunction "8_8") (pintype "passive"))
      (node (ref "U20") (pin "15") (pinfunction "OE#_15") (pintype "input"))
      (node (ref "U20") (pin "8") (pinfunction "GND_8") (pintype "power_in"))
      (node (ref "U21") (pin "A2") (pinfunction "GND_A2") (pintype "power_in"))
    )
    (net (code "224") (name "Net-(U1B-USBHS_RREF)") (class "Default")
      (node (ref "R80") (pin "2") (pinfunction "2_2") (pintype "passive"))
      (node (ref "U1") (pin "J15") (pinfunction "USBHS_RREF_J15") (pintype "input"))
    )
    (net (code "225") (name "Net-(U1E-P304)") (class "Default")
      (node (ref "R59") (pin "2") (pinfunction "2_2") (pintype "passive"))
      (node (ref "U1") (pin "D10") (pinfunction "P304_D10") (pintype "bidirectional"))
    )
    (net (code "226") (name "Net-(U1E-P305)") (class "Default")
      (node (ref "R60") (pin "2") (pinfunction "2_2") (pintype "passive"))
      (node (ref "U1") (pin "C10") (pinfunction "P305_C10") (pintype "bidirectional"))
    )
    (net (code "227") (name "Net-(U1E-P306)") (class "Default")
      (node (ref "R61") (pin "2") (pinfunction "2_2") (pintype "passive"))
      (node (ref "U1") (pin "D11") (pinfunction "P306_D11") (pintype "bidirectional"))
    )
    (net (code "228") (name "Net-(U1E-P307)") (class "Default")
      (node (ref "R62") (pin "2") (pinfunction "2_2") (pintype "passive"))
      (node (ref "U1") (pin "C11") (pinfunction "P307_C11") (pintype "bidirectional"))
    )
    (net (code "229") (name "Net-(U1E-P309)") (class "Default")
      (node (ref "R63") (pin "2") (pinfunction "2_2") (pintype "passive"))
      (node (ref "U1") (pin "A12") (pinfunction "P309_A12") (pintype "bidirectional"))
    )
    (net (code "230") (name "Net-(U1E-P310)") (class "Default")
      (node (ref "R64") (pin "2") (pinfunction "2_2") (pintype "passive"))
      (node (ref "U1") (pin "E10") (pinfunction "P310_E10") (pintype "bidirectional"))
    )
    (net (code "231") (name "Net-(U20-3B2)") (class "Default")
      (node (ref "E53") (pin "1") (pinfunction "1_1") (pintype "passive"))
      (node (ref "U20") (pin "10") (pinfunction "3B2_10") (pintype "bidirectional"))
    )
    (net (code "232") (name "Net-(U20-4B2)") (class "Default")
      (node (ref "E54") (pin "1") (pinfunction "1_1") (pintype "passive"))
      (node (ref "U20") (pin "13") (pinfunction "4B2_13") (pintype "bidirectional"))
    )
    (net (code "233") (name "Net-(U21-D3N)") (class "Default")
      (node (ref "RA22") (pin "7") (pinfunction "7_7") (pintype "passive"))
      (node (ref "U21") (pin "C5") (pinfunction "D3N_C5") (pintype "bidirectional"))
    )
    (net (code "234") (name "Net-(U21-D3P)") (class "Default")
      (node (ref "RA22") (pin "8") (pinfunction "8_8") (pintype "passive"))
      (node (ref "U21") (pin "C6") (pinfunction "D3P_C6") (pintype "bidirectional"))
    )
    (net (code "235") (name "Net-(U21-D4N)") (class "Default")
      (node (ref "RA22") (pin "5") (pinfunction "5_5") (pintype "passive"))
      (node (ref "U21") (pin "B5") (pinfunction "D4N_B5") (pintype "bidirectional"))
    )
    (net (code "236") (name "Net-(U21-D4P)") (class "Default")
      (node (ref "RA22") (pin "6") (pinfunction "6_6") (pintype "passive"))
      (node (ref "U21") (pin "B6") (pinfunction "D4P_B6") (pintype "bidirectional"))
    )
    (net (code "237") (name "Net-(U21-DA3N)") (class "Default")
      (node (ref "RA23") (pin "2") (pinfunction "2_2") (pintype "passive"))
      (node (ref "U21") (pin "B3") (pinfunction "DA3N_B3") (pintype "bidirectional"))
    )
    (net (code "238") (name "Net-(U21-DA3P)") (class "Default")
      (node (ref "RA23") (pin "1") (pinfunction "1_1") (pintype "passive"))
      (node (ref "U21") (pin "B4") (pinfunction "DA3P_B4") (pintype "bidirectional"))
    )
    (net (code "239") (name "Net-(U21-DA4N)") (class "Default")
      (node (ref "RA23") (pin "4") (pinfunction "4_4") (pintype "passive"))
      (node (ref "U21") (pin "A3") (pinfunction "DA4N_A3") (pintype "bidirectional"))
    )
    (net (code "240") (name "Net-(U21-DA4P)") (class "Default")
      (node (ref "RA23") (pin "3") (pinfunction "3_3") (pintype "passive"))
      (node (ref "U21") (pin "A4") (pinfunction "DA4P_A4") (pintype "bidirectional"))
    )
    (net (code "241") (name "Net-(U21-DB3N)") (class "Default")
      (node (ref "RA24") (pin "2") (pinfunction "2_2") (pintype "passive"))
      (node (ref "U21") (pin "C1") (pinfunction "DB3N_C1") (pintype "bidirectional"))
    )
    (net (code "242") (name "Net-(U21-DB3P)") (class "Default")
      (node (ref "RA24") (pin "1") (pinfunction "1_1") (pintype "passive"))
      (node (ref "U21") (pin "C2") (pinfunction "DB3P_C2") (pintype "bidirectional"))
    )
    (net (code "243") (name "Net-(U21-DB4N)") (class "Default")
      (node (ref "RA24") (pin "4") (pinfunction "4_4") (pintype "passive"))
      (node (ref "U21") (pin "B1") (pinfunction "DB4N_B1") (pintype "bidirectional"))
    )
    (net (code "244") (name "Net-(U21-DB4P)") (class "Default")
      (node (ref "RA24") (pin "3") (pinfunction "3_3") (pintype "passive"))
      (node (ref "U21") (pin "B2") (pinfunction "DB4P_B2") (pintype "bidirectional"))
    )
    (net (code "245") (name "P3V3") (class "Default")
      (node (ref "C31") (pin "2") (pinfunction "2_2") (pintype "passive"))
      (node (ref "C83") (pin "2") (pinfunction "2_2") (pintype "passive"))
      (node (ref "C91") (pin "2") (pinfunction "2_2") (pintype "passive"))
      (node (ref "R14") (pin "2") (pinfunction "2_2") (pintype "passive"))
      (node (ref "R26") (pin "2") (pinfunction "2_2") (pintype "passive"))
      (node (ref "R28") (pin "2") (pinfunction "2_2") (pintype "passive"))
      (node (ref "R71") (pin "1") (pinfunction "1_1") (pintype "passive"))
      (node (ref "U20") (pin "16") (pinfunction "VCC_16") (pintype "power_in"))
      (node (ref "U21") (pin "A1") (pinfunction "VDD_A1") (pintype "power_in"))
    )
    (net (code "246") (name "VSS_USBHS") (class "Default")
      (node (ref "R80") (pin "1") (pinfunction "1_1") (pintype "passive"))
    )
    (net (code "247") (name "unconnected-(U20-3B1-Pad11)") (class "Default")
      (node (ref "U20") (pin "11") (pinfunction "3B1_11") (pintype "bidirectional+no_connect"))
    )
    (net (code "248") (name "unconnected-(U20-4B1-Pad14)") (class "Default")
      (node (ref "U20") (pin "14") (pinfunction "4B1_14") (pintype "bidirectional+no_connect"))
    )
    (net (code "249") (name "unconnected-(U21-NC-PadC3)") (class "Default")
      (node (ref "U21") (pin "C3") (pinfunction "NC_C3") (pintype "bidirectional+no_connect"))
    )
    (net (code "250") (name "unconnected-(U21-NC-PadC4)") (class "Default")
      (node (ref "U21") (pin "C4") (pinfunction "NC_C4") (pintype "bidirectional+no_connect"))
    )
  )
)
